# mcuPower.net
KiCad netlist of a schematic drawn in EAGLE
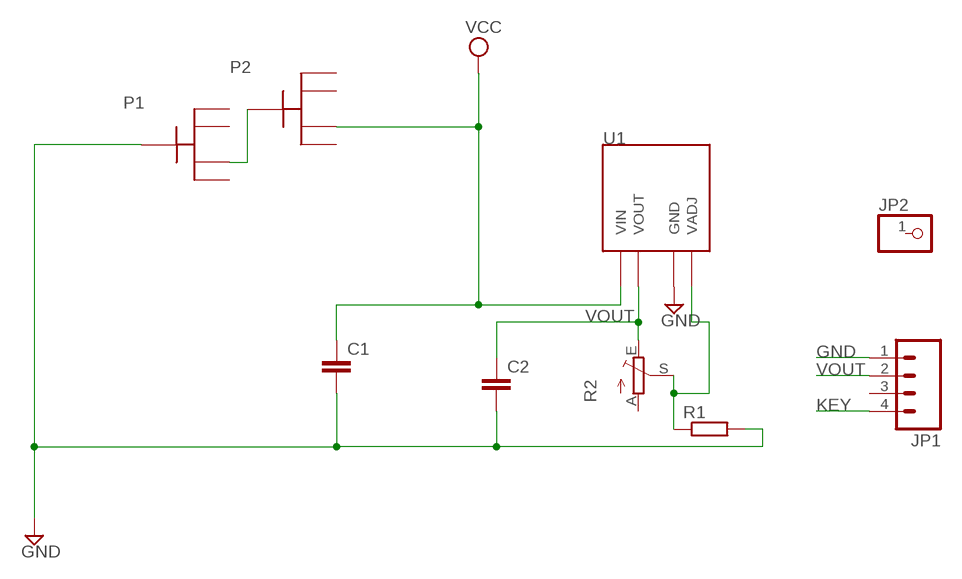
[diagram p0: schematic, sheet 1]

(export (version "E")
  (design (tool "Eeschema 10.0.6"))
  (components
    (comp (ref "C1")
      (value "C-EUC0805")
      (footprint "eagle-import:C0805")
      (libsource (lib "eagle-import") (part "C-EUC0805"))
    )
    (comp (ref "C2")
      (value "C-EUC0805")
      (footprint "eagle-import:C0805")
      (libsource (lib "eagle-import") (part "C-EUC0805"))
    )
    (comp (ref "JP1")
      (value "M04PTH")
      (footprint "eagle-import:1X04")
      (libsource (lib "eagle-import") (part "M04PTH"))
    )
    (comp (ref "JP2")
      (value "PINHD-1X1")
      (footprint "eagle-import:1X01")
      (libsource (lib "eagle-import") (part "PINHD-1X1"))
    )
    (comp (ref "P1")
      (value "CR2032")
      (footprint "eagle-import:CR2032_2025")
      (libsource (lib "eagle-import") (part "CR2032"))
    )
    (comp (ref "P2")
      (value "CR2032")
      (footprint "eagle-import:CR2032_2025")
      (libsource (lib "eagle-import") (part "CR2032"))
    )
    (comp (ref "R1")
      (value "R-EU_R0805")
      (footprint "eagle-import:R0805")
      (libsource (lib "eagle-import") (part "R-EU_R0805"))
    )
    (comp (ref "R2")
      (value "TRIM_EU-B25P")
      (footprint "eagle-import:B25P")
      (libsource (lib "eagle-import") (part "TRIM_EU-B25P"))
    )
    (comp (ref "U1")
      (value "PQ070XF01SZH")
      (footprint "eagle-import:TO220-4")
      (libsource (lib "eagle-import") (part "PQ070XF01SZH"))
    )
  )
  (nets
    (net (code "1") (name "/KEY") (class "Default")
      (node (ref "JP1") (pin "4") (pinfunction "4_4") (pintype "passive"))
    )
    (net (code "2") (name "/VOUT") (class "Default")
      (node (ref "C2") (pin "1") (pinfunction "1_1") (pintype "passive"))
      (node (ref "JP1") (pin "2") (pinfunction "2_2") (pintype "passive"))
      (node (ref "R2") (pin "E") (pinfunction "E_E") (pintype "passive"))
      (node (ref "U1") (pin "VOUT") (pinfunction "VOUT_VOUT") (pintype "bidirectional"))
    )
    (net (code "3") (name "GND") (class "Default")
      (node (ref "C1") (pin "2") (pinfunction "2_2") (pintype "passive"))
      (node (ref "C2") (pin "2") (pinfunction "2_2") (pintype "passive"))
      (node (ref "JP1") (pin "1") (pinfunction "1_1") (pintype "passive"))
      (node (ref "P1") (pin "GND") (pinfunction "GND_GND") (pintype "bidirectional"))
      (node (ref "R1") (pin "2") (pinfunction "2_2") (pintype "passive"))
      (node (ref "U1") (pin "GND") (pinfunction "GND_GND") (pintype "bidirectional"))
    )
    (net (code "4") (name "Net-(P1-PadVCC_3)") (class "Default")
      (node (ref "P1") (pin "VCC_3") (pinfunction "VCC_3_VCC_3") (pintype "bidirectional"))
      (node (ref "P2") (pin "GND") (pinfunction "GND_GND") (pintype "bidirectional"))
    )
    (net (code "5") (name "Net-(R1-Pad1)") (class "Default")
      (node (ref "R1") (pin "1") (pinfunction "1_1") (pintype "passive"))
      (node (ref "R2") (pin "S") (pinfunction "S_S") (pintype "passive"))
      (node (ref "U1") (pin "VADJ") (pinfunction "VADJ_VADJ") (pintype "bidirectional"))
    )
    (net (code "6") (name "VCC") (class "Default")
      (node (ref "C1") (pin "1") (pinfunction "1_1") (pintype "passive"))
      (node (ref "P2") (pin "VCC_3") (pinfunction "VCC_3_VCC_3") (pintype "bidirectional"))
      (node (ref "U1") (pin "VIN") (pinfunction "VIN_VIN") (pintype "bidirectional"))
    )
    (net (code "7") (name "unconnected-(JP1-Pad3)") (class "Default")
      (node (ref "JP1") (pin "3") (pinfunction "3_3") (pintype "passive"))
    )
    (net (code "8") (name "unconnected-(JP2-Pad1)") (class "Default")
      (node (ref "JP2") (pin "1") (pinfunction "1_1") (pintype "passive"))
    )
    (net (code "9") (name "unconnected-(P1-PadVCC_1)") (class "Default")
      (node (ref "P1") (pin "VCC_1") (pinfunction "VCC_1_VCC_1") (pintype "bidirectional"))
    )
    (net (code "10") (name "unconnected-(P1-PadVCC_2)") (class "Default")
      (node (ref "P1") (pin "VCC_2") (pinfunction "VCC_2_VCC_2") (pintype "bidirectional"))
    )
    (net (code "11") (name "unconnected-(P1-PadVCC_4)") (class "Default")
      (node (ref "P1") (pin "VCC_4") (pinfunction "VCC_4_VCC_4") (pintype "bidirectional"))
    )
    (net (code "12") (name "unconnected-(P2-PadVCC_1)") (class "Default")
      (node (ref "P2") (pin "VCC_1") (pinfunction "VCC_1_VCC_1") (pintype "bidirectional"))
    )
    (net (code "13") (name "unconnected-(P2-PadVCC_2)") (class "Default")
      (node (ref "P2") (pin "VCC_2") (pinfunction "VCC_2_VCC_2") (pintype "bidirectional"))
    )
    (net (code "14") (name "unconnected-(P2-PadVCC_4)") (class "Default")
      (node (ref "P2") (pin "VCC_4") (pinfunction "VCC_4_VCC_4") (pintype "bidirectional"))
    )
    (net (code "15") (name "unconnected-(R2-PadA)") (class "Default")
      (node (ref "R2") (pin "A") (pinfunction "A_A") (pintype "passive"))
    )
  )
)
